# Power_Distribution_-_Spares_1-5.net
KiCad netlist of a schematic drawn in Altium Designer
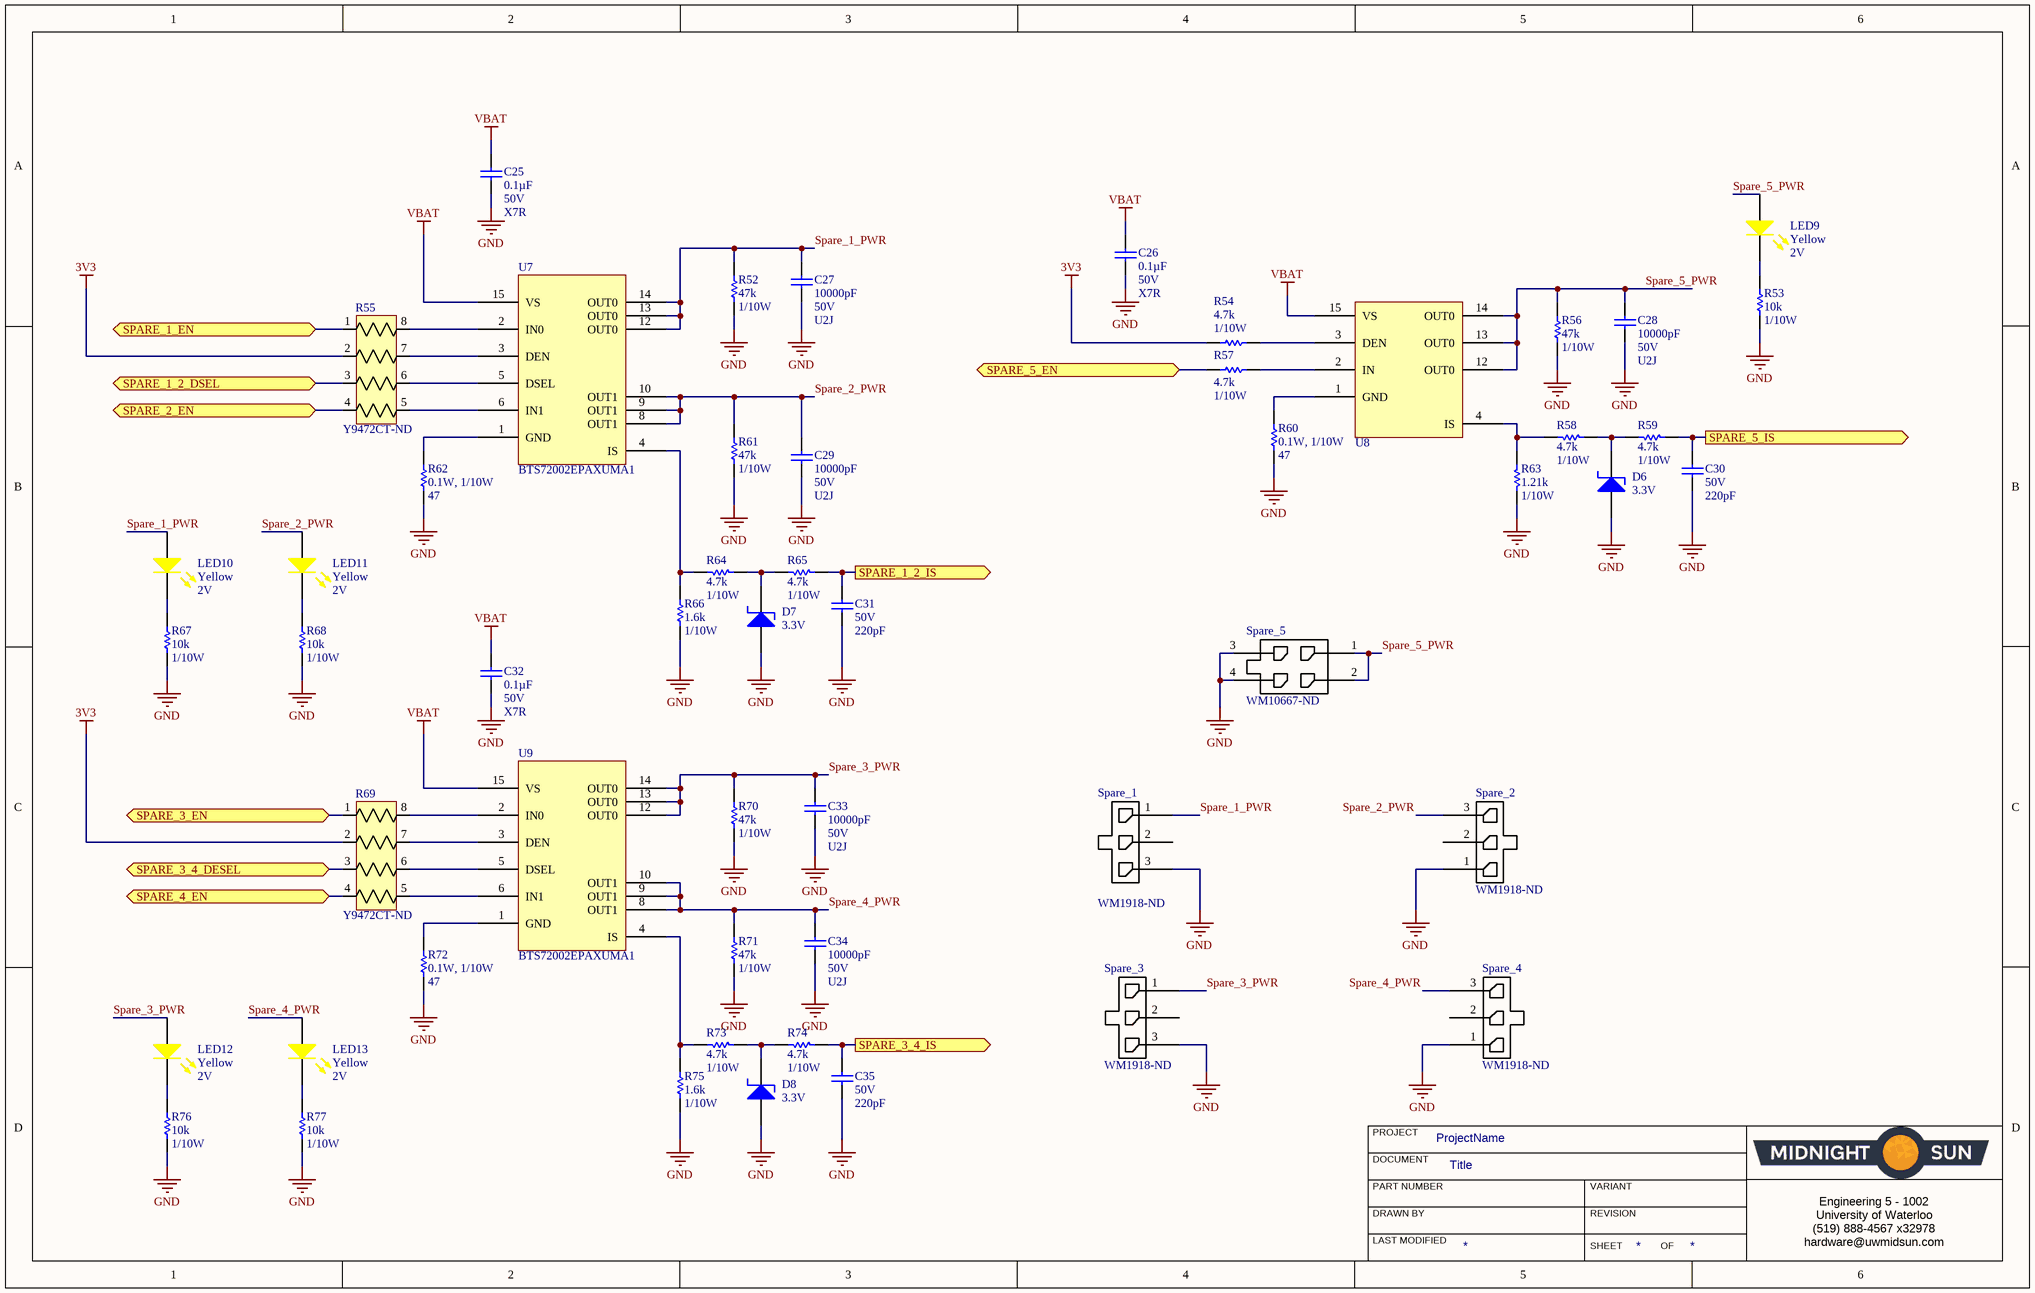
[diagram p0: Power Distribution - Spares 1-5.SchDoc]

(export (version "E")
  (design (tool "Eeschema 10.0.6"))
  (components
    (comp (ref "C25")
      (value "CAP CER 0.1UF 50V 10% X7R 0603")
      (footprint "CAP, 0603")
      (description "0.10µF ±10% 50V Ceramic Capacitor X7R 0603 (1608 Metric)")
      (fields
        (field (name "TOLERANCE") "±10%")
        (field (name "CAPACITANCE") "0.1µF")
        (field (name "VOLTAGE") "50V")
        (field (name "TEMPERATURE COEFFICIENT") "X7R")
      )
      (libsource (lib "Schematic Diagrams") (part "CAP CER 0.1UF 50V 10% X7R 0603"))
    )
    (comp (ref "C26")
      (value "CAP CER 0.1UF 50V 10% X7R 0603")
      (footprint "CAP, 0603")
      (description "0.10µF ±10% 50V Ceramic Capacitor X7R 0603 (1608 Metric)")
      (fields
        (field (name "TOLERANCE") "±10%")
        (field (name "CAPACITANCE") "0.1µF")
        (field (name "VOLTAGE") "50V")
        (field (name "TEMPERATURE COEFFICIENT") "X7R")
      )
      (libsource (lib "Schematic Diagrams") (part "CAP CER 0.1UF 50V 10% X7R 0603"))
    )
    (comp (ref "C27")
      (value "CAP CER 10nF 50V 5% X7R 0603")
      (footprint "CAP, 0603")
      (description "10000pF ±5% 50V Ceramic Capacitor U2J 0603 (1608 Metric)")
      (fields
        (field (name "TOLERANCE") "±5%")
        (field (name "CAPACITANCE") "10000pF")
        (field (name "VOLTAGE") "50V")
        (field (name "TEMPERATURE COEFFICIENT") "U2J")
      )
      (libsource (lib "Schematic Diagrams") (part "CAP CER 10nF 50V 5% X7R 0603"))
    )
    (comp (ref "C28")
      (value "CAP CER 10nF 50V 5% X7R 0603")
      (footprint "CAP, 0603")
      (description "10000pF ±5% 50V Ceramic Capacitor U2J 0603 (1608 Metric)")
      (fields
        (field (name "TOLERANCE") "±5%")
        (field (name "CAPACITANCE") "10000pF")
        (field (name "VOLTAGE") "50V")
        (field (name "TEMPERATURE COEFFICIENT") "U2J")
      )
      (libsource (lib "Schematic Diagrams") (part "CAP CER 10nF 50V 5% X7R 0603"))
    )
    (comp (ref "C29")
      (value "CAP CER 10nF 50V 5% X7R 0603")
      (footprint "CAP, 0603")
      (description "10000pF ±5% 50V Ceramic Capacitor U2J 0603 (1608 Metric)")
      (fields
        (field (name "TOLERANCE") "±5%")
        (field (name "CAPACITANCE") "10000pF")
        (field (name "VOLTAGE") "50V")
        (field (name "TEMPERATURE COEFFICIENT") "U2J")
      )
      (libsource (lib "Schematic Diagrams") (part "CAP CER 10nF 50V 5% X7R 0603"))
    )
    (comp (ref "C30")
      (value "CAP CER 220PF 50V C0G/NP0 0603")
      (footprint "CAP, 0603")
      (description "220pF ±5% 50V Ceramic Capacitor C0G, NP0 0603 (1608 Metric)")
      (fields
        (field (name "MANUFACTURER") "KEMET")
        (field (name "TOLERANCE") "5%")
        (field (name "VOLTAGE RATING") "50V")
        (field (name "CAPACITANCE") "220pF")
      )
      (libsource (lib "Schematic Diagrams") (part "CAP CER 220PF 50V C0G/NP0 0603"))
    )
    (comp (ref "C31")
      (value "CAP CER 220PF 50V C0G/NP0 0603")
      (footprint "CAP, 0603")
      (description "220pF ±5% 50V Ceramic Capacitor C0G, NP0 0603 (1608 Metric)")
      (fields
        (field (name "MANUFACTURER") "KEMET")
        (field (name "TOLERANCE") "5%")
        (field (name "VOLTAGE RATING") "50V")
        (field (name "CAPACITANCE") "220pF")
      )
      (libsource (lib "Schematic Diagrams") (part "CAP CER 220PF 50V C0G/NP0 0603"))
    )
    (comp (ref "C32")
      (value "CAP CER 0.1UF 50V 10% X7R 0603")
      (footprint "CAP, 0603")
      (description "0.10µF ±10% 50V Ceramic Capacitor X7R 0603 (1608 Metric)")
      (fields
        (field (name "TOLERANCE") "±10%")
        (field (name "CAPACITANCE") "0.1µF")
        (field (name "VOLTAGE") "50V")
        (field (name "TEMPERATURE COEFFICIENT") "X7R")
      )
      (libsource (lib "Schematic Diagrams") (part "CAP CER 0.1UF 50V 10% X7R 0603"))
    )
    (comp (ref "C33")
      (value "CAP CER 10nF 50V 5% X7R 0603")
      (footprint "CAP, 0603")
      (description "10000pF ±5% 50V Ceramic Capacitor U2J 0603 (1608 Metric)")
      (fields
        (field (name "TOLERANCE") "±5%")
        (field (name "CAPACITANCE") "10000pF")
        (field (name "VOLTAGE") "50V")
        (field (name "TEMPERATURE COEFFICIENT") "U2J")
      )
      (libsource (lib "Schematic Diagrams") (part "CAP CER 10nF 50V 5% X7R 0603"))
    )
    (comp (ref "C34")
      (value "CAP CER 10nF 50V 5% X7R 0603")
      (footprint "CAP, 0603")
      (description "10000pF ±5% 50V Ceramic Capacitor U2J 0603 (1608 Metric)")
      (fields
        (field (name "TOLERANCE") "±5%")
        (field (name "CAPACITANCE") "10000pF")
        (field (name "VOLTAGE") "50V")
        (field (name "TEMPERATURE COEFFICIENT") "U2J")
      )
      (libsource (lib "Schematic Diagrams") (part "CAP CER 10nF 50V 5% X7R 0603"))
    )
    (comp (ref "C35")
      (value "CAP CER 220PF 50V C0G/NP0 0603")
      (footprint "CAP, 0603")
      (description "220pF ±5% 50V Ceramic Capacitor C0G, NP0 0603 (1608 Metric)")
      (fields
        (field (name "MANUFACTURER") "KEMET")
        (field (name "TOLERANCE") "5%")
        (field (name "VOLTAGE RATING") "50V")
        (field (name "CAPACITANCE") "220pF")
      )
      (libsource (lib "Schematic Diagrams") (part "CAP CER 220PF 50V C0G/NP0 0603"))
    )
    (comp (ref "D6")
      (value "DIODE ZENER 3.3V 200MW SOD323")
      (footprint "sod-323")
      (description "Zener Diode 3.3V 200mW ±5% Surface Mount SOD-323")
      (fields (field (name "VOLTAGE") "3.3V"))
      (libsource (lib "Schematic Diagrams") (part "DIODE ZENER 3.3V 200MW SOD323"))
    )
    (comp (ref "D7")
      (value "DIODE ZENER 3.3V 200MW SOD323")
      (footprint "sod-323")
      (description "Zener Diode 3.3V 200mW ±5% Surface Mount SOD-323")
      (fields (field (name "VOLTAGE") "3.3V"))
      (libsource (lib "Schematic Diagrams") (part "DIODE ZENER 3.3V 200MW SOD323"))
    )
    (comp (ref "D8")
      (value "DIODE ZENER 3.3V 200MW SOD323")
      (footprint "sod-323")
      (description "Zener Diode 3.3V 200mW ±5% Surface Mount SOD-323")
      (fields (field (name "VOLTAGE") "3.3V"))
      (libsource (lib "Schematic Diagrams") (part "DIODE ZENER 3.3V 200MW SOD323"))
    )
    (comp (ref "LED9")
      (value "LED YELLOW CLEAR 2.1V 0603")
      (footprint "LED_0603")
      (description "Yellow 590nm LED Indication - Discrete 2V 0603 (1608 Metric)")
      (fields
        (field (name "MANUFACTURER") "Wurth Electronics Inc.")
        (field (name "MANUFACTURER PART NUMBER") "150060YS75000")
        (field (name "COLOR") "Yellow")
        (field (name "VOLTAGE - FORWARD (VF) (TYP)") "2V")
      )
      (libsource (lib "Schematic Diagrams") (part "LED YELLOW CLEAR 2.1V 0603"))
    )
    (comp (ref "LED10")
      (value "LED YELLOW CLEAR 2.1V 0603")
      (footprint "LED_0603")
      (description "Yellow 590nm LED Indication - Discrete 2V 0603 (1608 Metric)")
      (fields
        (field (name "MANUFACTURER") "Wurth Electronics Inc.")
        (field (name "MANUFACTURER PART NUMBER") "150060YS75000")
        (field (name "COLOR") "Yellow")
        (field (name "VOLTAGE - FORWARD (VF) (TYP)") "2V")
      )
      (libsource (lib "Schematic Diagrams") (part "LED YELLOW CLEAR 2.1V 0603"))
    )
    (comp (ref "LED11")
      (value "LED YELLOW CLEAR 2.1V 0603")
      (footprint "LED_0603")
      (description "Yellow 590nm LED Indication - Discrete 2V 0603 (1608 Metric)")
      (fields
        (field (name "MANUFACTURER") "Wurth Electronics Inc.")
        (field (name "MANUFACTURER PART NUMBER") "150060YS75000")
        (field (name "COLOR") "Yellow")
        (field (name "VOLTAGE - FORWARD (VF) (TYP)") "2V")
      )
      (libsource (lib "Schematic Diagrams") (part "LED YELLOW CLEAR 2.1V 0603"))
    )
    (comp (ref "LED12")
      (value "LED YELLOW CLEAR 2.1V 0603")
      (footprint "LED_0603")
      (description "Yellow 590nm LED Indication - Discrete 2V 0603 (1608 Metric)")
      (fields
        (field (name "MANUFACTURER") "Wurth Electronics Inc.")
        (field (name "MANUFACTURER PART NUMBER") "150060YS75000")
        (field (name "COLOR") "Yellow")
        (field (name "VOLTAGE - FORWARD (VF) (TYP)") "2V")
      )
      (libsource (lib "Schematic Diagrams") (part "LED YELLOW CLEAR 2.1V 0603"))
    )
    (comp (ref "LED13")
      (value "LED YELLOW CLEAR 2.1V 0603")
      (footprint "LED_0603")
      (description "Yellow 590nm LED Indication - Discrete 2V 0603 (1608 Metric)")
      (fields
        (field (name "MANUFACTURER") "Wurth Electronics Inc.")
        (field (name "MANUFACTURER PART NUMBER") "150060YS75000")
        (field (name "COLOR") "Yellow")
        (field (name "VOLTAGE - FORWARD (VF) (TYP)") "2V")
      )
      (libsource (lib "Schematic Diagrams") (part "LED YELLOW CLEAR 2.1V 0603"))
    )
    (comp (ref "R52")
      (value "RES 47K OHM 1% 1/10W 0603")
      (footprint "RES, 0603")
      (description "47 kOhms ±1% 0.1W, 1/10W Chip Resistor 0603 (1608 Metric) Automotive AEC-Q200 Thick Film")
      (fields
        (field (name "MANUFACTURER") "Panasonic")
        (field (name "MANUFACTURER PART NUMBER") "ERJ3EKF4702V")
        (field (name "RESISTANCE") "47k")
        (field (name "POWER RATING") "1/10W")
      )
      (libsource (lib "Schematic Diagrams") (part "RES 47K OHM 1% 1/10W 0603"))
    )
    (comp (ref "R53")
      (value "RES 10K OHM 1% 1/10W 0603")
      (footprint "RES, 0603")
      (description "RES SMD 10K OHM 1% 1/10W 0603")
      (fields
        (field (name "TOLERANCE") "±1%")
        (field (name "RESISTANCE") "10k")
        (field (name "POWER") "1/10W")
      )
      (libsource (lib "Schematic Diagrams") (part "RES 10K OHM 1% 1/10W 0603"))
    )
    (comp (ref "R54")
      (value "RES 4.7K OHM 1% 1/10W 0603")
      (footprint "RES, 0603")
      (description "4.7k Ohm ±1% 0.1W, 1/10W Chip Resistor 0603 (1608 Metric) Moisture Resistant Thick Film")
      (fields
        (field (name "TOLERANCE") "±1%")
        (field (name "RESISTANCE (OHMS)") "4.7k")
        (field (name "POWER (WATTS)") "1/10W")
      )
      (libsource (lib "Schematic Diagrams") (part "RES 4.7K OHM 1% 1/10W 0603"))
    )
    (comp (ref "R55")
      (value "RES ARRAY 4 RES 4.7K OHM 1206")
      (footprint "RES ARRAY 4RES 1206")
      (fields (field (name "TOLERANCE") "±5%") (field (name "SUPPLIER PART NUMBER 1") "Y9472CT-ND"))
      (libsource (lib "Schematic Diagrams") (part "RES ARRAY 4 RES 4.7K OHM 1206"))
    )
    (comp (ref "R56")
      (value "RES 47K OHM 1% 1/10W 0603")
      (footprint "RES, 0603")
      (description "47 kOhms ±1% 0.1W, 1/10W Chip Resistor 0603 (1608 Metric) Automotive AEC-Q200 Thick Film")
      (fields
        (field (name "MANUFACTURER") "Panasonic")
        (field (name "MANUFACTURER PART NUMBER") "ERJ3EKF4702V")
        (field (name "RESISTANCE") "47k")
        (field (name "POWER RATING") "1/10W")
      )
      (libsource (lib "Schematic Diagrams") (part "RES 47K OHM 1% 1/10W 0603"))
    )
    (comp (ref "R57")
      (value "RES 4.7K OHM 1% 1/10W 0603")
      (footprint "RES, 0603")
      (description "4.7k Ohm ±1% 0.1W, 1/10W Chip Resistor 0603 (1608 Metric) Moisture Resistant Thick Film")
      (fields
        (field (name "TOLERANCE") "±1%")
        (field (name "RESISTANCE (OHMS)") "4.7k")
        (field (name "POWER (WATTS)") "1/10W")
      )
      (libsource (lib "Schematic Diagrams") (part "RES 4.7K OHM 1% 1/10W 0603"))
    )
    (comp (ref "R58")
      (value "RES 4.7K OHM 1% 1/10W 0603")
      (footprint "RES, 0603")
      (description "4.7k Ohm ±1% 0.1W, 1/10W Chip Resistor 0603 (1608 Metric) Moisture Resistant Thick Film")
      (fields
        (field (name "TOLERANCE") "±1%")
        (field (name "RESISTANCE (OHMS)") "4.7k")
        (field (name "POWER (WATTS)") "1/10W")
      )
      (libsource (lib "Schematic Diagrams") (part "RES 4.7K OHM 1% 1/10W 0603"))
    )
    (comp (ref "R59")
      (value "RES 4.7K OHM 1% 1/10W 0603")
      (footprint "RES, 0603")
      (description "4.7k Ohm ±1% 0.1W, 1/10W Chip Resistor 0603 (1608 Metric) Moisture Resistant Thick Film")
      (fields
        (field (name "TOLERANCE") "±1%")
        (field (name "RESISTANCE (OHMS)") "4.7k")
        (field (name "POWER (WATTS)") "1/10W")
      )
      (libsource (lib "Schematic Diagrams") (part "RES 4.7K OHM 1% 1/10W 0603"))
    )
    (comp (ref "R60")
      (value "RES SMD 47 OHM 1% 1/10W 0603")
      (footprint "RES, 0603")
      (fields
        (field (name "TOLERANCE") "±1%")
        (field (name "POWER (WATTS)") "0.1W, 1/10W")
        (field (name "VALUES") "47")
      )
      (libsource (lib "Schematic Diagrams") (part "RES SMD 47 OHM 1% 1/10W 0603"))
    )
    (comp (ref "R61")
      (value "RES 47K OHM 1% 1/10W 0603")
      (footprint "RES, 0603")
      (description "47 kOhms ±1% 0.1W, 1/10W Chip Resistor 0603 (1608 Metric) Automotive AEC-Q200 Thick Film")
      (fields
        (field (name "MANUFACTURER") "Panasonic")
        (field (name "MANUFACTURER PART NUMBER") "ERJ3EKF4702V")
        (field (name "RESISTANCE") "47k")
        (field (name "POWER RATING") "1/10W")
      )
      (libsource (lib "Schematic Diagrams") (part "RES 47K OHM 1% 1/10W 0603"))
    )
    (comp (ref "R62")
      (value "RES SMD 47 OHM 1% 1/10W 0603")
      (footprint "RES, 0603")
      (fields
        (field (name "TOLERANCE") "±1%")
        (field (name "POWER (WATTS)") "0.1W, 1/10W")
        (field (name "VALUES") "47")
      )
      (libsource (lib "Schematic Diagrams") (part "RES SMD 47 OHM 1% 1/10W 0603"))
    )
    (comp (ref "R63")
      (value "RES 1.21K OHM 1% 1/10W 0603")
      (footprint "RES, 0603")
      (description "1.21k Ohm ±1% 0.1W, 1/10W Chip Resistor 0603 (1608 Metric) Moisture Resistant Thick Film")
      (fields
        (field (name "TOLERANCE") "±1%")
        (field (name "RESISTANCE") "1.21k")
        (field (name "POWER") "1/10W")
      )
      (libsource (lib "Schematic Diagrams") (part "RES 1.21K OHM 1% 1/10W 0603"))
    )
    (comp (ref "R64")
      (value "RES 4.7K OHM 1% 1/10W 0603")
      (footprint "RES, 0603")
      (description "4.7k Ohm ±1% 0.1W, 1/10W Chip Resistor 0603 (1608 Metric) Moisture Resistant Thick Film")
      (fields
        (field (name "TOLERANCE") "±1%")
        (field (name "RESISTANCE (OHMS)") "4.7k")
        (field (name "POWER (WATTS)") "1/10W")
      )
      (libsource (lib "Schematic Diagrams") (part "RES 4.7K OHM 1% 1/10W 0603"))
    )
    (comp (ref "R65")
      (value "RES 4.7K OHM 1% 1/10W 0603")
      (footprint "RES, 0603")
      (description "4.7k Ohm ±1% 0.1W, 1/10W Chip Resistor 0603 (1608 Metric) Moisture Resistant Thick Film")
      (fields
        (field (name "TOLERANCE") "±1%")
        (field (name "RESISTANCE (OHMS)") "4.7k")
        (field (name "POWER (WATTS)") "1/10W")
      )
      (libsource (lib "Schematic Diagrams") (part "RES 4.7K OHM 1% 1/10W 0603"))
    )
    (comp (ref "R66")
      (value "RES 1.6K OHM 1% 1/10W 0603")
      (footprint "RES, 0603")
      (description "1.6 kOhms ±1% 0.1W, 1/10W Chip Resistor 0603 (1608 Metric) Moisture Resistant Thick Film")
      (fields
        (field (name "MANUFACTURER") "Yageo")
        (field (name "MANUFACTURER PART NUMBER") "RC0603FR-071K6L")
        (field (name "RESISTANCE") "1.6k")
        (field (name "POWER RATING") "1/10W")
      )
      (libsource (lib "Schematic Diagrams") (part "RES 1.6K OHM 1% 1/10W 0603"))
    )
    (comp (ref "R67")
      (value "RES 10K OHM 1% 1/10W 0603")
      (footprint "RES, 0603")
      (description "RES SMD 10K OHM 1% 1/10W 0603")
      (fields
        (field (name "TOLERANCE") "±1%")
        (field (name "RESISTANCE") "10k")
        (field (name "POWER") "1/10W")
      )
      (libsource (lib "Schematic Diagrams") (part "RES 10K OHM 1% 1/10W 0603"))
    )
    (comp (ref "R68")
      (value "RES 10K OHM 1% 1/10W 0603")
      (footprint "RES, 0603")
      (description "RES SMD 10K OHM 1% 1/10W 0603")
      (fields
        (field (name "TOLERANCE") "±1%")
        (field (name "RESISTANCE") "10k")
        (field (name "POWER") "1/10W")
      )
      (libsource (lib "Schematic Diagrams") (part "RES 10K OHM 1% 1/10W 0603"))
    )
    (comp (ref "R69")
      (value "RES ARRAY 4 RES 4.7K OHM 1206")
      (footprint "RES ARRAY 4RES 1206")
      (fields (field (name "TOLERANCE") "±5%") (field (name "SUPPLIER PART NUMBER 1") "Y9472CT-ND"))
      (libsource (lib "Schematic Diagrams") (part "RES ARRAY 4 RES 4.7K OHM 1206"))
    )
    (comp (ref "R70")
      (value "RES 47K OHM 1% 1/10W 0603")
      (footprint "RES, 0603")
      (description "47 kOhms ±1% 0.1W, 1/10W Chip Resistor 0603 (1608 Metric) Automotive AEC-Q200 Thick Film")
      (fields
        (field (name "MANUFACTURER") "Panasonic")
        (field (name "MANUFACTURER PART NUMBER") "ERJ3EKF4702V")
        (field (name "RESISTANCE") "47k")
        (field (name "POWER RATING") "1/10W")
      )
      (libsource (lib "Schematic Diagrams") (part "RES 47K OHM 1% 1/10W 0603"))
    )
    (comp (ref "R71")
      (value "RES 47K OHM 1% 1/10W 0603")
      (footprint "RES, 0603")
      (description "47 kOhms ±1% 0.1W, 1/10W Chip Resistor 0603 (1608 Metric) Automotive AEC-Q200 Thick Film")
      (fields
        (field (name "MANUFACTURER") "Panasonic")
        (field (name "MANUFACTURER PART NUMBER") "ERJ3EKF4702V")
        (field (name "RESISTANCE") "47k")
        (field (name "POWER RATING") "1/10W")
      )
      (libsource (lib "Schematic Diagrams") (part "RES 47K OHM 1% 1/10W 0603"))
    )
    (comp (ref "R72")
      (value "RES SMD 47 OHM 1% 1/10W 0603")
      (footprint "RES, 0603")
      (fields
        (field (name "TOLERANCE") "±1%")
        (field (name "POWER (WATTS)") "0.1W, 1/10W")
        (field (name "VALUES") "47")
      )
      (libsource (lib "Schematic Diagrams") (part "RES SMD 47 OHM 1% 1/10W 0603"))
    )
    (comp (ref "R73")
      (value "RES 4.7K OHM 1% 1/10W 0603")
      (footprint "RES, 0603")
      (description "4.7k Ohm ±1% 0.1W, 1/10W Chip Resistor 0603 (1608 Metric) Moisture Resistant Thick Film")
      (fields
        (field (name "TOLERANCE") "±1%")
        (field (name "RESISTANCE (OHMS)") "4.7k")
        (field (name "POWER (WATTS)") "1/10W")
      )
      (libsource (lib "Schematic Diagrams") (part "RES 4.7K OHM 1% 1/10W 0603"))
    )
    (comp (ref "R74")
      (value "RES 4.7K OHM 1% 1/10W 0603")
      (footprint "RES, 0603")
      (description "4.7k Ohm ±1% 0.1W, 1/10W Chip Resistor 0603 (1608 Metric) Moisture Resistant Thick Film")
      (fields
        (field (name "TOLERANCE") "±1%")
        (field (name "RESISTANCE (OHMS)") "4.7k")
        (field (name "POWER (WATTS)") "1/10W")
      )
      (libsource (lib "Schematic Diagrams") (part "RES 4.7K OHM 1% 1/10W 0603"))
    )
    (comp (ref "R75")
      (value "RES 1.6K OHM 1% 1/10W 0603")
      (footprint "RES, 0603")
      (description "1.6 kOhms ±1% 0.1W, 1/10W Chip Resistor 0603 (1608 Metric) Moisture Resistant Thick Film")
      (fields
        (field (name "MANUFACTURER") "Yageo")
        (field (name "MANUFACTURER PART NUMBER") "RC0603FR-071K6L")
        (field (name "RESISTANCE") "1.6k")
        (field (name "POWER RATING") "1/10W")
      )
      (libsource (lib "Schematic Diagrams") (part "RES 1.6K OHM 1% 1/10W 0603"))
    )
    (comp (ref "R76")
      (value "RES 10K OHM 1% 1/10W 0603")
      (footprint "RES, 0603")
      (description "RES SMD 10K OHM 1% 1/10W 0603")
      (fields
        (field (name "TOLERANCE") "±1%")
        (field (name "RESISTANCE") "10k")
        (field (name "POWER") "1/10W")
      )
      (libsource (lib "Schematic Diagrams") (part "RES 10K OHM 1% 1/10W 0603"))
    )
    (comp (ref "R77")
      (value "RES 10K OHM 1% 1/10W 0603")
      (footprint "RES, 0603")
      (description "RES SMD 10K OHM 1% 1/10W 0603")
      (fields
        (field (name "TOLERANCE") "±1%")
        (field (name "RESISTANCE") "10k")
        (field (name "POWER") "1/10W")
      )
      (libsource (lib "Schematic Diagrams") (part "RES 10K OHM 1% 1/10W 0603"))
    )
    (comp (ref "Spare_1")
      (value "CONN 3POS MICROFIT")
      (footprint "CONN, 3 POS MICROFIT")
      (description "Connector Header Through Hole 3 position 0.118\" (3.00mm)")
      (fields (field (name "SUPPLIER PART NUMBER 1") "WM1918-ND"))
      (libsource (lib "Schematic Diagrams") (part "CONN 3POS MICROFIT"))
    )
    (comp (ref "Spare_2")
      (value "CONN 3POS MICROFIT")
      (footprint "CONN, 3 POS MICROFIT")
      (description "Connector Header Through Hole 3 position 0.118\" (3.00mm)")
      (fields (field (name "SUPPLIER PART NUMBER 1") "WM1918-ND"))
      (libsource (lib "Schematic Diagrams") (part "CONN 3POS MICROFIT"))
    )
    (comp (ref "Spare_3")
      (value "CONN 3POS MICROFIT")
      (footprint "CONN, 3 POS MICROFIT")
      (description "Connector Header Through Hole 3 position 0.118\" (3.00mm)")
      (fields (field (name "SUPPLIER PART NUMBER 1") "WM1918-ND"))
      (libsource (lib "Schematic Diagrams") (part "CONN 3POS MICROFIT"))
    )
    (comp (ref "Spare_4")
      (value "CONN 3POS MICROFIT")
      (footprint "CONN, 3 POS MICROFIT")
      (description "Connector Header Through Hole 3 position 0.118\" (3.00mm)")
      (fields (field (name "SUPPLIER PART NUMBER 1") "WM1918-ND"))
      (libsource (lib "Schematic Diagrams") (part "CONN 3POS MICROFIT"))
    )
    (comp (ref "Spare_5")
      (value "CONN 4POS MICRO-FIT 3mm")
      (footprint "CONN 4POS MICROFIT (2x2)")
      (fields
        (field (name "MANUFACTURER") "Molex, LLC")
        (field (name "MANUFACTURER PART NUMBER") "430450427")
        (field (name "SUPPLIER PART NUMBER 1") "WM10667-ND")
      )
      (libsource (lib "Schematic Diagrams") (part "CONN 4POS MICRO-FIT 3mm"))
    )
    (comp (ref "U7")
      (value "IC LOAD SWITCH BTS7200-2EPA PG-TSDSO-14_1")
      (footprint "IC LOAD SWITCH PG-TSDSO-14-22")
      (description "Power Switch/Driver 1:1 N-Channel 1.2A PG-TSDSO-14-22")
      (fields
        (field (name "MANUFACTURER") "Infineon")
        (field (name "MANUFACTURER PART NUMBER") "BTS72002EPAXUMA1")
      )
      (libsource (lib "Schematic Diagrams") (part "IC LOAD SWITCH BTS7200-2EPA PG-TSDSO-14_1"))
    )
    (comp (ref "U8")
      (value "IC LOAD SWITCH BTS70401EPA PG-TSDSO-14-22")
      (footprint "IC LOAD SWITCH PG-TSDSO-14-22")
      (description "Power Switch/Driver 1:1 N-Channel 4.5A PG-TSDSO-14-22")
      (fields
        (field (name "MANUFACTURER") "Infineon")
        (field (name "MANUFACTURER PART NUMBER") "BTS70401EPAXUMA1")
      )
      (libsource (lib "Schematic Diagrams") (part "IC LOAD SWITCH BTS70401EPA PG-TSDSO-14-22"))
    )
    (comp (ref "U9")
      (value "IC LOAD SWITCH BTS7200-2EPA PG-TSDSO-14_1")
      (footprint "IC LOAD SWITCH PG-TSDSO-14-22")
      (description "Power Switch/Driver 1:1 N-Channel 1.2A PG-TSDSO-14-22")
      (fields
        (field (name "MANUFACTURER") "Infineon")
        (field (name "MANUFACTURER PART NUMBER") "BTS72002EPAXUMA1")
      )
      (libsource (lib "Schematic Diagrams") (part "IC LOAD SWITCH BTS7200-2EPA PG-TSDSO-14_1"))
    )
  )
  (nets
    (net (code "1") (name "/SPARE_1_2_DSEL") (class "Default")
      (node (ref "R55") (pin "3") (pinfunction "3_3") (pintype "passive"))
    )
    (net (code "2") (name "/SPARE_1_2_IS") (class "Default")
      (node (ref "C31") (pin "1") (pinfunction "1_1") (pintype "passive"))
      (node (ref "R65") (pin "1") (pinfunction "1_1") (pintype "passive"))
    )
    (net (code "3") (name "/SPARE_1_EN") (class "Default")
      (node (ref "R55") (pin "1") (pinfunction "1_1") (pintype "passive"))
    )
    (net (code "4") (name "/SPARE_2_EN") (class "Default")
      (node (ref "R55") (pin "4") (pinfunction "4_4") (pintype "passive"))
    )
    (net (code "5") (name "/SPARE_3_4_DESEL") (class "Default")
      (node (ref "R69") (pin "3") (pinfunction "3_3") (pintype "passive"))
    )
    (net (code "6") (name "/SPARE_3_4_IS") (class "Default")
      (node (ref "C35") (pin "1") (pinfunction "1_1") (pintype "passive"))
      (node (ref "R74") (pin "1") (pinfunction "1_1") (pintype "passive"))
    )
    (net (code "7") (name "/SPARE_3_EN") (class "Default")
      (node (ref "R69") (pin "1") (pinfunction "1_1") (pintype "passive"))
    )
    (net (code "8") (name "/SPARE_4_EN") (class "Default")
      (node (ref "R69") (pin "4") (pinfunction "4_4") (pintype "passive"))
    )
    (net (code "9") (name "/SPARE_5_EN") (class "Default")
      (node (ref "R57") (pin "1") (pinfunction "1_1") (pintype "passive"))
    )
    (net (code "10") (name "/SPARE_5_IS") (class "Default")
      (node (ref "C30") (pin "1") (pinfunction "1_1") (pintype "passive"))
      (node (ref "R59") (pin "1") (pinfunction "1_1") (pintype "passive"))
    )
    (net (code "11") (name "/Spare_1_PWR") (class "Default")
      (node (ref "C27") (pin "1") (pinfunction "1_1") (pintype "passive"))
      (node (ref "LED10") (pin "1") (pinfunction "A_1") (pintype "passive"))
      (node (ref "R52") (pin "1") (pinfunction "1_1") (pintype "passive"))
      (node (ref "Spare_1") (pin "1") (pinfunction "1_1") (pintype "passive"))
      (node (ref "U7") (pin "12") (pinfunction "OUT0_12") (pintype "passive"))
      (node (ref "U7") (pin "13") (pinfunction "OUT0_13") (pintype "passive"))
      (node (ref "U7") (pin "14") (pinfunction "OUT0_14") (pintype "passive"))
    )
    (net (code "12") (name "/Spare_2_PWR") (class "Default")
      (node (ref "C29") (pin "1") (pinfunction "1_1") (pintype "passive"))
      (node (ref "LED11") (pin "1") (pinfunction "A_1") (pintype "passive"))
      (node (ref "R61") (pin "1") (pinfunction "1_1") (pintype "passive"))
      (node (ref "Spare_2") (pin "3") (pinfunction "3_3") (pintype "passive"))
      (node (ref "U7") (pin "10") (pinfunction "OUT1_10") (pintype "passive"))
      (node (ref "U7") (pin "8") (pinfunction "OUT1_8") (pintype "passive"))
      (node (ref "U7") (pin "9") (pinfunction "OUT1_9") (pintype "passive"))
    )
    (net (code "13") (name "/Spare_3_PWR") (class "Default")
      (node (ref "C33") (pin "1") (pinfunction "1_1") (pintype "passive"))
      (node (ref "LED12") (pin "1") (pinfunction "A_1") (pintype "passive"))
      (node (ref "R70") (pin "1") (pinfunction "1_1") (pintype "passive"))
      (node (ref "Spare_3") (pin "1") (pinfunction "1_1") (pintype "passive"))
      (node (ref "U9") (pin "12") (pinfunction "OUT0_12") (pintype "passive"))
      (node (ref "U9") (pin "13") (pinfunction "OUT0_13") (pintype "passive"))
      (node (ref "U9") (pin "14") (pinfunction "OUT0_14") (pintype "passive"))
    )
    (net (code "14") (name "/Spare_4_PWR") (class "Default")
      (node (ref "C34") (pin "1") (pinfunction "1_1") (pintype "passive"))
      (node (ref "LED13") (pin "1") (pinfunction "A_1") (pintype "passive"))
      (node (ref "R71") (pin "1") (pinfunction "1_1") (pintype "passive"))
      (node (ref "Spare_4") (pin "3") (pinfunction "3_3") (pintype "passive"))
      (node (ref "U9") (pin "10") (pinfunction "OUT1_10") (pintype "passive"))
      (node (ref "U9") (pin "8") (pinfunction "OUT1_8") (pintype "passive"))
      (node (ref "U9") (pin "9") (pinfunction "OUT1_9") (pintype "passive"))
    )
    (net (code "15") (name "/Spare_5_PWR") (class "Default")
      (node (ref "C28") (pin "1") (pinfunction "1_1") (pintype "passive"))
      (node (ref "LED9") (pin "1") (pinfunction "A_1") (pintype "passive"))
      (node (ref "R56") (pin "1") (pinfunction "1_1") (pintype "passive"))
      (node (ref "Spare_5") (pin "1") (pinfunction "1_1") (pintype "passive"))
      (node (ref "Spare_5") (pin "2") (pinfunction "2_2") (pintype "passive"))
      (node (ref "U8") (pin "12") (pinfunction "OUT0_12") (pintype "passive"))
      (node (ref "U8") (pin "13") (pinfunction "OUT0_13") (pintype "passive"))
      (node (ref "U8") (pin "14") (pinfunction "OUT0_14") (pintype "passive"))
    )
    (net (code "16") (name "3V3") (class "Default")
      (node (ref "R54") (pin "1") (pinfunction "1_1") (pintype "passive"))
      (node (ref "R55") (pin "2") (pinfunction "2_2") (pintype "passive"))
      (node (ref "R69") (pin "2") (pinfunction "2_2") (pintype "passive"))
    )
    (net (code "17") (name "GND") (class "Default")
      (node (ref "C25") (pin "2") (pinfunction "2_2") (pintype "passive"))
      (node (ref "C26") (pin "2") (pinfunction "2_2") (pintype "passive"))
      (node (ref "C27") (pin "2") (pinfunction "2_2") (pintype "passive"))
      (node (ref "C28") (pin "2") (pinfunction "2_2") (pintype "passive"))
      (node (ref "C29") (pin "2") (pinfunction "2_2") (pintype "passive"))
      (node (ref "C30") (pin "2") (pinfunction "2_2") (pintype "passive"))
      (node (ref "C31") (pin "2") (pinfunction "2_2") (pintype "passive"))
      (node (ref "C32") (pin "2") (pinfunction "2_2") (pintype "passive"))
      (node (ref "C33") (pin "2") (pinfunction "2_2") (pintype "passive"))
      (node (ref "C34") (pin "2") (pinfunction "2_2") (pintype "passive"))
      (node (ref "C35") (pin "2") (pinfunction "2_2") (pintype "passive"))
      (node (ref "D6") (pin "1") (pinfunction "A_1") (pintype "passive"))
      (node (ref "D7") (pin "1") (pinfunction "A_1") (pintype "passive"))
      (node (ref "D8") (pin "1") (pinfunction "A_1") (pintype "passive"))
      (node (ref "R52") (pin "2") (pinfunction "2_2") (pintype "passive"))
      (node (ref "R53") (pin "2") (pinfunction "2_2") (pintype "passive"))
      (node (ref "R56") (pin "2") (pinfunction "2_2") (pintype "passive"))
      (node (ref "R60") (pin "2") (pinfunction "2_2") (pintype "passive"))
      (node (ref "R61") (pin "2") (pinfunction "2_2") (pintype "passive"))
      (node (ref "R62") (pin "2") (pinfunction "2_2") (pintype "passive"))
      (node (ref "R63") (pin "2") (pinfunction "2_2") (pintype "passive"))
      (node (ref "R66") (pin "2") (pinfunction "2_2") (pintype "passive"))
      (node (ref "R67") (pin "2") (pinfunction "2_2") (pintype "passive"))
      (node (ref "R68") (pin "2") (pinfunction "2_2") (pintype "passive"))
      (node (ref "R70") (pin "2") (pinfunction "2_2") (pintype "passive"))
      (node (ref "R71") (pin "2") (pinfunction "2_2") (pintype "passive"))
      (node (ref "R72") (pin "2") (pinfunction "2_2") (pintype "passive"))
      (node (ref "R75") (pin "2") (pinfunction "2_2") (pintype "passive"))
      (node (ref "R76") (pin "2") (pinfunction "2_2") (pintype "passive"))
      (node (ref "R77") (pin "2") (pinfunction "2_2") (pintype "passive"))
      (node (ref "Spare_1") (pin "3") (pinfunction "3_3") (pintype "passive"))
      (node (ref "Spare_2") (pin "1") (pinfunction "1_1") (pintype "passive"))
      (node (ref "Spare_3") (pin "3") (pinfunction "3_3") (pintype "passive"))
      (node (ref "Spare_4") (pin "1") (pinfunction "1_1") (pintype "passive"))
      (node (ref "Spare_5") (pin "3") (pinfunction "3_3") (pintype "passive"))
      (node (ref "Spare_5") (pin "4") (pinfunction "4_4") (pintype "passive"))
    )
    (net (code "18") (name "Net-(D6-K)") (class "Default")
      (node (ref "D6") (pin "2") (pinfunction "K_2") (pintype "passive"))
      (node (ref "R58") (pin "1") (pinfunction "1_1") (pintype "passive"))
      (node (ref "R59") (pin "2") (pinfunction "2_2") (pintype "passive"))
    )
    (net (code "19") (name "Net-(D7-K)") (class "Default")
      (node (ref "D7") (pin "2") (pinfunction "K_2") (pintype "passive"))
      (node (ref "R64") (pin "1") (pinfunction "1_1") (pintype "passive"))
      (node (ref "R65") (pin "2") (pinfunction "2_2") (pintype "passive"))
    )
    (net (code "20") (name "Net-(D8-K)") (class "Default")
      (node (ref "D8") (pin "2") (pinfunction "K_2") (pintype "passive"))
      (node (ref "R73") (pin "1") (pinfunction "1_1") (pintype "passive"))
      (node (ref "R74") (pin "2") (pinfunction "2_2") (pintype "passive"))
    )
    (net (code "21") (name "Net-(LED9-K)") (class "Default")
      (node (ref "LED9") (pin "2") (pinfunction "K_2") (pintype "passive"))
      (node (ref "R53") (pin "1") (pinfunction "1_1") (pintype "passive"))
    )
    (net (code "22") (name "Net-(LED10-K)") (class "Default")
      (node (ref "LED10") (pin "2") (pinfunction "K_2") (pintype "passive"))
      (node (ref "R67") (pin "1") (pinfunction "1_1") (pintype "passive"))
    )
    (net (code "23") (name "Net-(LED11-K)") (class "Default")
      (node (ref "LED11") (pin "2") (pinfunction "K_2") (pintype "passive"))
      (node (ref "R68") (pin "1") (pinfunction "1_1") (pintype "passive"))
    )
    (net (code "24") (name "Net-(LED12-K)") (class "Default")
      (node (ref "LED12") (pin "2") (pinfunction "K_2") (pintype "passive"))
      (node (ref "R76") (pin "1") (pinfunction "1_1") (pintype "passive"))
    )
    (net (code "25") (name "Net-(LED13-K)") (class "Default")
      (node (ref "LED13") (pin "2") (pinfunction "K_2") (pintype "passive"))
      (node (ref "R77") (pin "1") (pinfunction "1_1") (pintype "passive"))
    )
    (net (code "26") (name "Net-(U7-DEN)") (class "Default")
      (node (ref "R55") (pin "7") (pinfunction "7_7") (pintype "passive"))
      (node (ref "U7") (pin "3") (pinfunction "DEN_3") (pintype "passive"))
    )
    (net (code "27") (name "Net-(U7-DSEL)") (class "Default")
      (node (ref "R55") (pin "6") (pinfunction "6_6") (pintype "passive"))
      (node (ref "U7") (pin "5") (pinfunction "DSEL_5") (pintype "passive"))
    )
    (net (code "28") (name "Net-(U7-GND)") (class "Default")
      (node (ref "R62") (pin "1") (pinfunction "1_1") (pintype "passive"))
      (node (ref "U7") (pin "1") (pinfunction "GND_1") (pintype "passive"))
    )
    (net (code "29") (name "Net-(U7-IN0)") (class "Default")
      (node (ref "R55") (pin "8") (pinfunction "8_8") (pintype "passive"))
      (node (ref "U7") (pin "2") (pinfunction "IN0_2") (pintype "passive"))
    )
    (net (code "30") (name "Net-(U7-IN1)") (class "Default")
      (node (ref "R55") (pin "5") (pinfunction "5_5") (pintype "passive"))
      (node (ref "U7") (pin "6") (pinfunction "IN1_6") (pintype "passive"))
    )
    (net (code "31") (name "Net-(U7-IS)") (class "Default")
      (node (ref "R64") (pin "2") (pinfunction "2_2") (pintype "passive"))
      (node (ref "R66") (pin "1") (pinfunction "1_1") (pintype "passive"))
      (node (ref "U7") (pin "4") (pinfunction "IS_4") (pintype "passive"))
    )
    (net (code "32") (name "Net-(U8-DEN)") (class "Default")
      (node (ref "R54") (pin "2") (pinfunction "2_2") (pintype "passive"))
      (node (ref "U8") (pin "3") (pinfunction "DEN_3") (pintype "passive"))
    )
    (net (code "33") (name "Net-(U8-GND)") (class "Default")
      (node (ref "R60") (pin "1") (pinfunction "1_1") (pintype "passive"))
      (node (ref "U8") (pin "1") (pinfunction "GND_1") (pintype "passive"))
    )
    (net (code "34") (name "Net-(U8-IN)") (class "Default")
      (node (ref "R57") (pin "2") (pinfunction "2_2") (pintype "passive"))
      (node (ref "U8") (pin "2") (pinfunction "IN_2") (pintype "passive"))
    )
    (net (code "35") (name "Net-(U8-IS)") (class "Default")
      (node (ref "R58") (pin "2") (pinfunction "2_2") (pintype "passive"))
      (node (ref "R63") (pin "1") (pinfunction "1_1") (pintype "passive"))
      (node (ref "U8") (pin "4") (pinfunction "IS_4") (pintype "passive"))
    )
    (net (code "36") (name "Net-(U9-DEN)") (class "Default")
      (node (ref "R69") (pin "7") (pinfunction "7_7") (pintype "passive"))
      (node (ref "U9") (pin "3") (pinfunction "DEN_3") (pintype "passive"))
    )
    (net (code "37") (name "Net-(U9-DSEL)") (class "Default")
      (node (ref "R69") (pin "6") (pinfunction "6_6") (pintype "passive"))
      (node (ref "U9") (pin "5") (pinfunction "DSEL_5") (pintype "passive"))
    )
    (net (code "38") (name "Net-(U9-GND)") (class "Default")
      (node (ref "R72") (pin "1") (pinfunction "1_1") (pintype "passive"))
      (node (ref "U9") (pin "1") (pinfunction "GND_1") (pintype "passive"))
    )
    (net (code "39") (name "Net-(U9-IN0)") (class "Default")
      (node (ref "R69") (pin "8") (pinfunction "8_8") (pintype "passive"))
      (node (ref "U9") (pin "2") (pinfunction "IN0_2") (pintype "passive"))
    )
    (net (code "40") (name "Net-(U9-IN1)") (class "Default")
      (node (ref "R69") (pin "5") (pinfunction "5_5") (pintype "passive"))
      (node (ref "U9") (pin "6") (pinfunction "IN1_6") (pintype "passive"))
    )
    (net (code "41") (name "Net-(U9-IS)") (class "Default")
      (node (ref "R73") (pin "2") (pinfunction "2_2") (pintype "passive"))
      (node (ref "R75") (pin "1") (pinfunction "1_1") (pintype "passive"))
      (node (ref "U9") (pin "4") (pinfunction "IS_4") (pintype "passive"))
    )
    (net (code "42") (name "VBAT") (class "Default")
      (node (ref "C25") (pin "1") (pinfunction "1_1") (pintype "passive"))
      (node (ref "C26") (pin "1") (pinfunction "1_1") (pintype "passive"))
      (node (ref "C32") (pin "1") (pinfunction "1_1") (pintype "passive"))
      (node (ref "U7") (pin "15") (pinfunction "VS_15") (pintype "passive"))
      (node (ref "U8") (pin "15") (pinfunction "VS_15") (pintype "passive"))
      (node (ref "U9") (pin "15") (pinfunction "VS_15") (pintype "passive"))
    )
    (net (code "43") (name "unconnected-(Spare_1-21-Pad2)") (class "Default")
      (node (ref "Spare_1") (pin "2") (pinfunction "21_2") (pintype "passive"))
    )
    (net (code "44") (name "unconnected-(Spare_2-21-Pad2)") (class "Default")
      (node (ref "Spare_2") (pin "2") (pinfunction "21_2") (pintype "passive"))
    )
    (net (code "45") (name "unconnected-(Spare_3-21-Pad2)") (class "Default")
      (node (ref "Spare_3") (pin "2") (pinfunction "21_2") (pintype "passive"))
    )
    (net (code "46") (name "unconnected-(Spare_4-21-Pad2)") (class "Default")
      (node (ref "Spare_4") (pin "2") (pinfunction "21_2") (pintype "passive"))
    )
  )
)
